# 03_-_MCU.net
KiCad netlist of a schematic drawn in Altium Designer
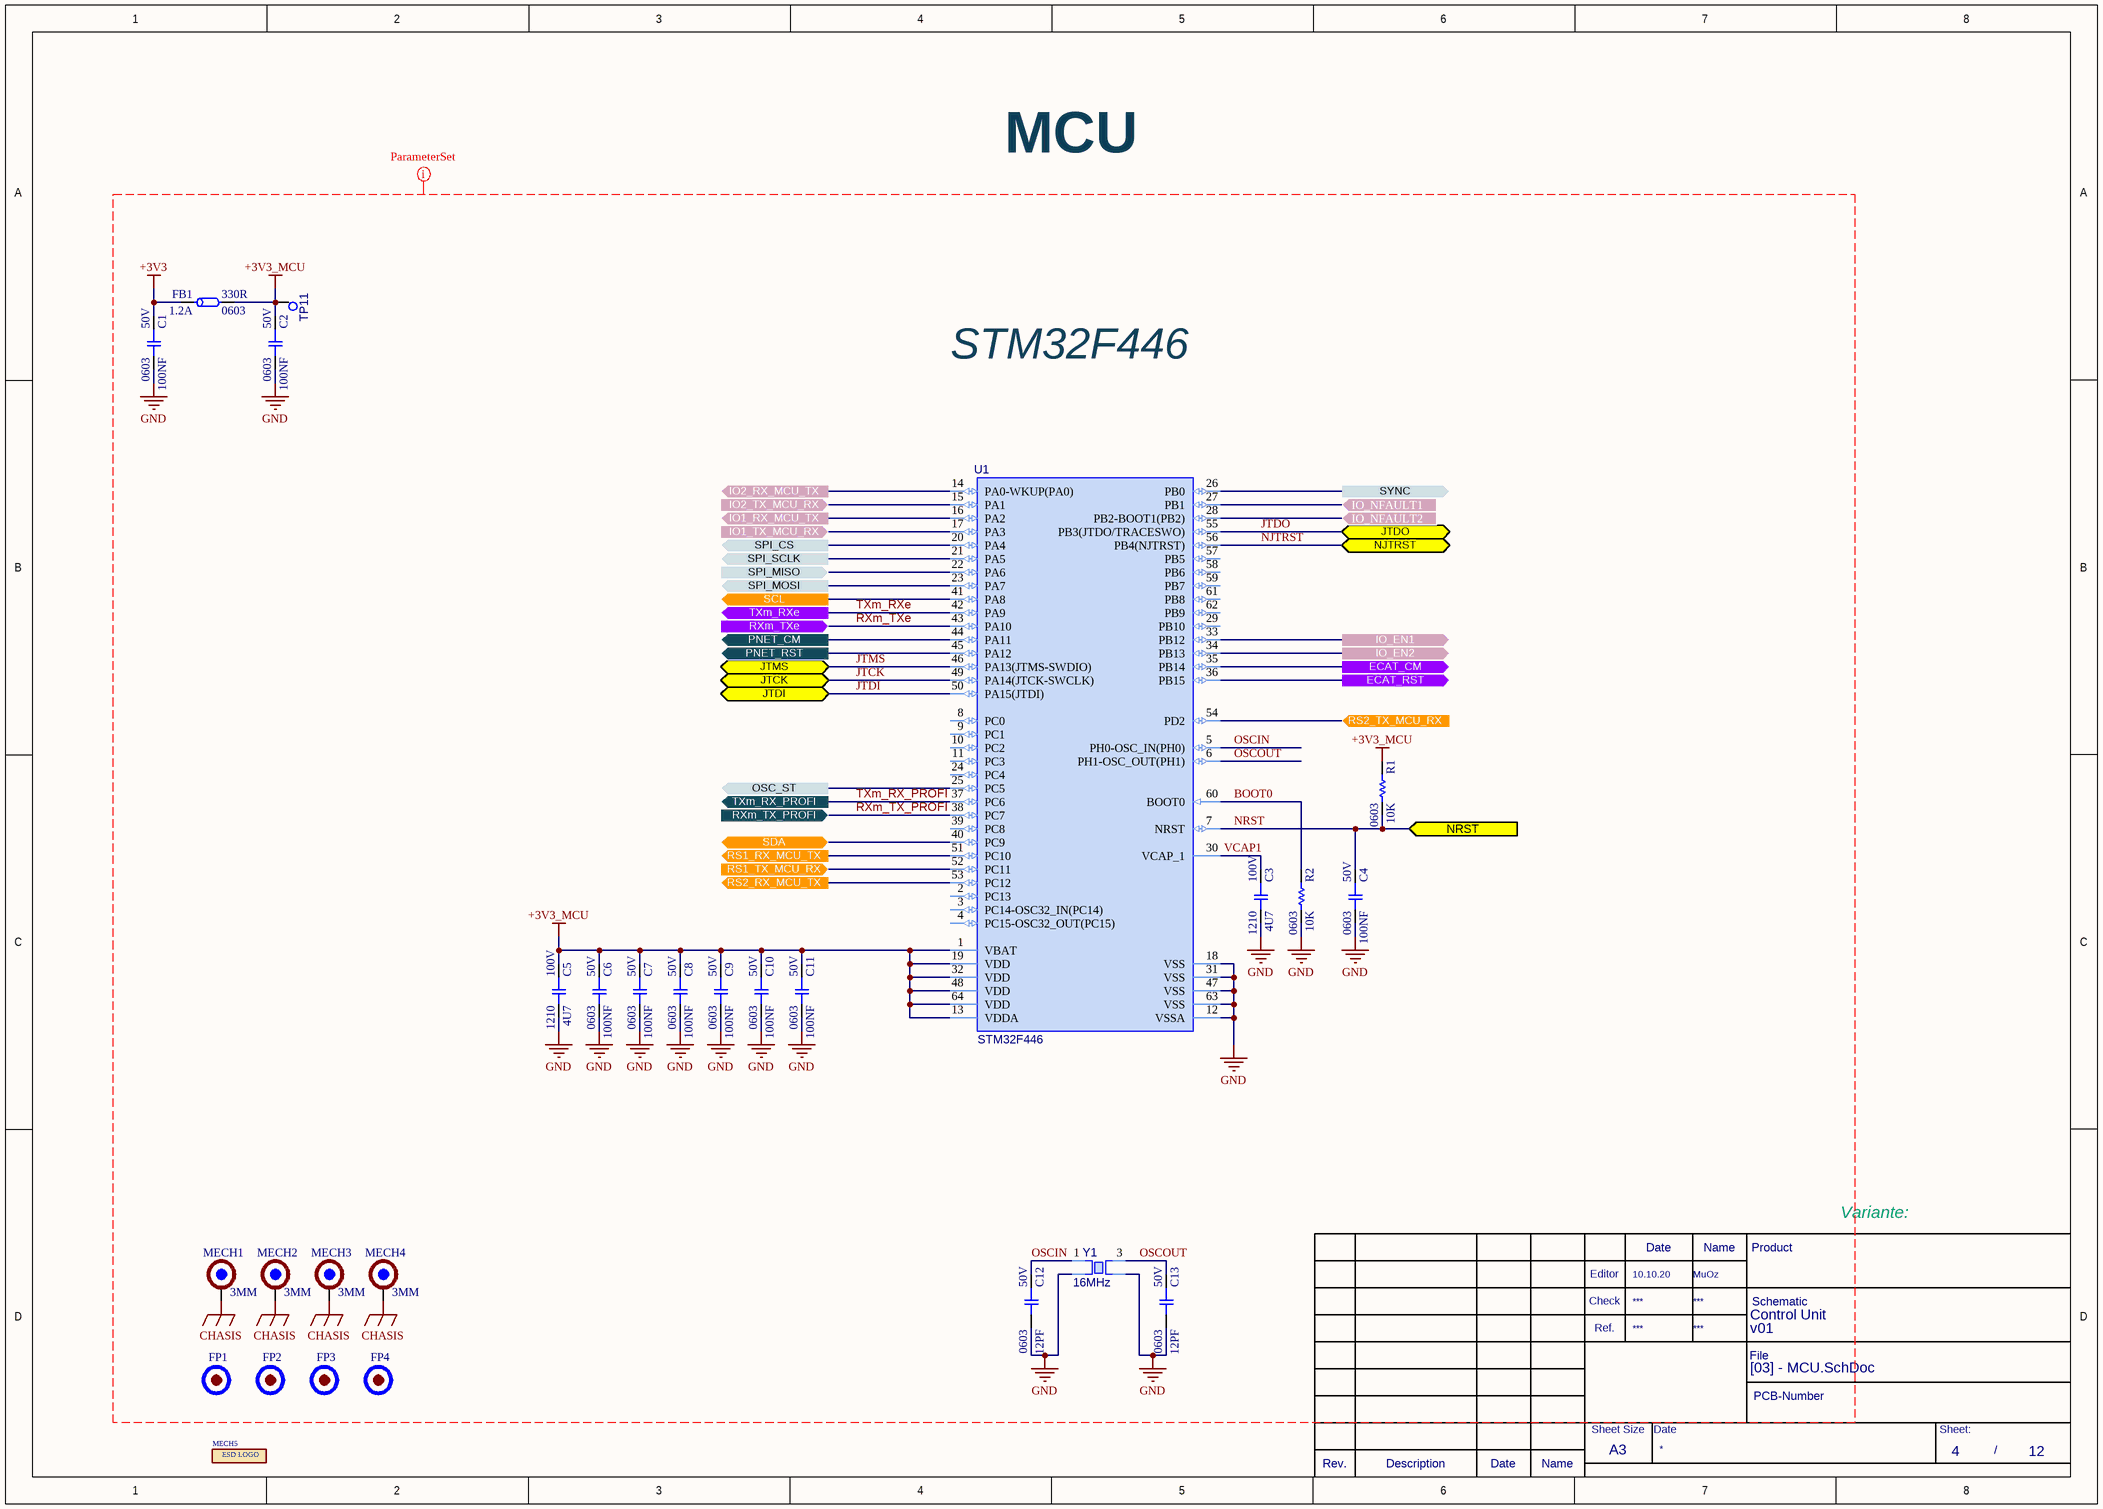
[diagram p0: [03] - MCU.SchDoc]

(export (version "E")
  (design (tool "Eeschema 10.0.6"))
  (components
    (comp (ref "C1")
      (value "100NF")
      (footprint "C-0603")
      (description "CAP CER 0.1UF 50V X7R 0603")
      (fields
        (field (name "MANUFACTURER") "TDK")
        (field (name "MANUFACTURER PART NUMBER") "C1608X7R1H104K080AA")
        (field (name "VOLTAGE RATING") "50V")
        (field (name "CASE CODE (IMPERIAL)") "0603")
        (field (name ".CREATOR") "F:TALI")
      )
      (libsource (lib "BARKO_SCHLIB") (part "C-100NF-0603"))
    )
    (comp (ref "C2")
      (value "100NF")
      (footprint "C-0603")
      (description "CAP CER 0.1UF 50V X7R 0603")
      (fields
        (field (name "MANUFACTURER") "TDK")
        (field (name "MANUFACTURER PART NUMBER") "C1608X7R1H104K080AA")
        (field (name "VOLTAGE RATING") "50V")
        (field (name "CASE CODE (IMPERIAL)") "0603")
        (field (name ".CREATOR") "F:TALI")
      )
      (libsource (lib "BARKO_SCHLIB") (part "C-100NF-0603"))
    )
    (comp (ref "C3")
      (value "4U7")
      (footprint "C-1210")
      (description "CAP CER 4.7UF 100V X7S 1210")
      (fields
        (field (name "MANUFACTURER") "Taiyo Yuden")
        (field (name "MANUFACTURER PART NUMBER") "HMK325C7475KM-PE")
        (field (name "CASE/PACKAGE") "1210")
        (field (name "VOLTAGE RATING") "100V")
        (field (name ".CREATOR") "M.OZKAN")
      )
      (libsource (lib "BARKO_SCHLIB") (part "C-4U7-1210-100V"))
    )
    (comp (ref "C4")
      (value "100NF")
      (footprint "C-0603")
      (description "CAP CER 0.1UF 50V X7R 0603")
      (fields
        (field (name "MANUFACTURER") "TDK")
        (field (name "MANUFACTURER PART NUMBER") "C1608X7R1H104K080AA")
        (field (name "VOLTAGE RATING") "50V")
        (field (name "CASE CODE (IMPERIAL)") "0603")
        (field (name ".CREATOR") "F:TALI")
      )
      (libsource (lib "BARKO_SCHLIB") (part "C-100NF-0603"))
    )
    (comp (ref "C5")
      (value "4U7")
      (footprint "C-1210")
      (description "CAP CER 4.7UF 100V X7S 1210")
      (fields
        (field (name "MANUFACTURER") "Taiyo Yuden")
        (field (name "MANUFACTURER PART NUMBER") "HMK325C7475KM-PE")
        (field (name "CASE/PACKAGE") "1210")
        (field (name "VOLTAGE RATING") "100V")
        (field (name ".CREATOR") "M.OZKAN")
      )
      (libsource (lib "BARKO_SCHLIB") (part "C-4U7-1210-100V"))
    )
    (comp (ref "C6")
      (value "100NF")
      (footprint "C-0603")
      (description "CAP CER 0.1UF 50V X7R 0603")
      (fields
        (field (name "MANUFACTURER") "TDK")
        (field (name "MANUFACTURER PART NUMBER") "C1608X7R1H104K080AA")
        (field (name "VOLTAGE RATING") "50V")
        (field (name "CASE CODE (IMPERIAL)") "0603")
        (field (name ".CREATOR") "F:TALI")
      )
      (libsource (lib "BARKO_SCHLIB") (part "C-100NF-0603"))
    )
    (comp (ref "C7")
      (value "100NF")
      (footprint "C-0603")
      (description "CAP CER 0.1UF 50V X7R 0603")
      (fields
        (field (name "MANUFACTURER") "TDK")
        (field (name "MANUFACTURER PART NUMBER") "C1608X7R1H104K080AA")
        (field (name "VOLTAGE RATING") "50V")
        (field (name "CASE CODE (IMPERIAL)") "0603")
        (field (name ".CREATOR") "F:TALI")
      )
      (libsource (lib "BARKO_SCHLIB") (part "C-100NF-0603"))
    )
    (comp (ref "C8")
      (value "100NF")
      (footprint "C-0603")
      (description "CAP CER 0.1UF 50V X7R 0603")
      (fields
        (field (name "MANUFACTURER") "TDK")
        (field (name "MANUFACTURER PART NUMBER") "C1608X7R1H104K080AA")
        (field (name "VOLTAGE RATING") "50V")
        (field (name "CASE CODE (IMPERIAL)") "0603")
        (field (name ".CREATOR") "F:TALI")
      )
      (libsource (lib "BARKO_SCHLIB") (part "C-100NF-0603"))
    )
    (comp (ref "C9")
      (value "100NF")
      (footprint "C-0603")
      (description "CAP CER 0.1UF 50V X7R 0603")
      (fields
        (field (name "MANUFACTURER") "TDK")
        (field (name "MANUFACTURER PART NUMBER") "C1608X7R1H104K080AA")
        (field (name "VOLTAGE RATING") "50V")
        (field (name "CASE CODE (IMPERIAL)") "0603")
        (field (name ".CREATOR") "F:TALI")
      )
      (libsource (lib "BARKO_SCHLIB") (part "C-100NF-0603"))
    )
    (comp (ref "C10")
      (value "100NF")
      (footprint "C-0603")
      (description "CAP CER 0.1UF 50V X7R 0603")
      (fields
        (field (name "MANUFACTURER") "TDK")
        (field (name "MANUFACTURER PART NUMBER") "C1608X7R1H104K080AA")
        (field (name "VOLTAGE RATING") "50V")
        (field (name "CASE CODE (IMPERIAL)") "0603")
        (field (name ".CREATOR") "F:TALI")
      )
      (libsource (lib "BARKO_SCHLIB") (part "C-100NF-0603"))
    )
    (comp (ref "C11")
      (value "100NF")
      (footprint "C-0603")
      (description "CAP CER 0.1UF 50V X7R 0603")
      (fields
        (field (name "MANUFACTURER") "TDK")
        (field (name "MANUFACTURER PART NUMBER") "C1608X7R1H104K080AA")
        (field (name "VOLTAGE RATING") "50V")
        (field (name "CASE CODE (IMPERIAL)") "0603")
        (field (name ".CREATOR") "F:TALI")
      )
      (libsource (lib "BARKO_SCHLIB") (part "C-100NF-0603"))
    )
    (comp (ref "C12")
      (value "12PF")
      (footprint "C-0603")
      (description "CAP CER 12PF 50V C0G/NP0 0603")
      (fields
        (field (name "MANUFACTURER") "Samsung")
        (field (name "MANUFACTURER PART NUMBER") "CL10C120JB8NNNC")
        (field (name "CASE CODE (IMPERIAL)") "0603")
        (field (name "VOLTAGE") "50V")
        (field (name ".CREATOR") "M.OZKAN")
      )
      (libsource (lib "BARKO_SCHLIB") (part "C-12PF-0603"))
    )
    (comp (ref "C13")
      (value "12PF")
      (footprint "C-0603")
      (description "CAP CER 12PF 50V C0G/NP0 0603")
      (fields
        (field (name "MANUFACTURER") "Samsung")
        (field (name "MANUFACTURER PART NUMBER") "CL10C120JB8NNNC")
        (field (name "CASE CODE (IMPERIAL)") "0603")
        (field (name "VOLTAGE") "50V")
        (field (name ".CREATOR") "M.OZKAN")
      )
      (libsource (lib "BARKO_SCHLIB") (part "C-12PF-0603"))
    )
    (comp (ref "FB1")
      (value "330R")
      (footprint "FB-0603")
      (description "FERRITE BEAD 330 OHM 0603 1LN")
      (fields
        (field (name "MANUFACTURER") "Murata")
        (field (name "MANUFACTURER PART NUMBER") "BLM18PG331SN1D")
        (field (name "CASE/PACKAGE") "0603")
        (field (name "DC CURRENT") "1.2A")
        (field (name ".CREATOR") "M.OZKAN")
      )
      (libsource (lib "BARKO_SCHLIB") (part "FB-330R-0603"))
    )
    (comp (ref "FP1")
      (value "MECH-Fiducial")
      (footprint "MECH-Fiducial")
      (fields (field (name ".CREATOR") "F:TALI"))
      (libsource (lib "BARKO_SCHLIB") (part "MECH-Fiducial"))
    )
    (comp (ref "FP2")
      (value "MECH-Fiducial")
      (footprint "MECH-Fiducial")
      (fields (field (name ".CREATOR") "F:TALI"))
      (libsource (lib "BARKO_SCHLIB") (part "MECH-Fiducial"))
    )
    (comp (ref "FP3")
      (value "MECH-Fiducial")
      (footprint "MECH-Fiducial")
      (fields (field (name ".CREATOR") "F:TALI"))
      (libsource (lib "BARKO_SCHLIB") (part "MECH-Fiducial"))
    )
    (comp (ref "FP4")
      (value "MECH-Fiducial")
      (footprint "MECH-Fiducial")
      (fields (field (name ".CREATOR") "F:TALI"))
      (libsource (lib "BARKO_SCHLIB") (part "MECH-Fiducial"))
    )
    (comp (ref "MECH1")
      (value "3MM")
      (footprint "MECH-3MM HOLE")
      (fields (field (name ".CREATOR") "F:TALI"))
      (libsource (lib "BARKO_SCHLIB") (part "MECH-3MM HOLE"))
    )
    (comp (ref "MECH2")
      (value "3MM")
      (footprint "MECH-3MM HOLE")
      (fields (field (name ".CREATOR") "F:TALI"))
      (libsource (lib "BARKO_SCHLIB") (part "MECH-3MM HOLE"))
    )
    (comp (ref "MECH3")
      (value "3MM")
      (footprint "MECH-3MM HOLE")
      (fields (field (name ".CREATOR") "F:TALI"))
      (libsource (lib "BARKO_SCHLIB") (part "MECH-3MM HOLE"))
    )
    (comp (ref "MECH4")
      (value "3MM")
      (footprint "MECH-3MM HOLE")
      (fields (field (name ".CREATOR") "F:TALI"))
      (libsource (lib "BARKO_SCHLIB") (part "MECH-3MM HOLE"))
    )
    (comp (ref "MECH5")
      (value "MECH-ESD-LOGO")
      (footprint "ESD_LOGO_4")
      (fields (field (name ".CREATOR") "F:TALI"))
      (libsource (lib "BARKO_SCHLIB") (part "MECH-ESD-LOGO"))
    )
    (comp (ref "R1")
      (value "10K")
      (footprint "R-0603")
      (description "RES SMD 10K OHM 1% 1/10W 0603")
      (fields
        (field (name "MANUFACTURER") "Yageo")
        (field (name "MANUFACTURER PART NUMBER") "RC0603FR-0710KL")
        (field (name "CASE CODE (IMPERIAL)") "0603")
        (field (name ".CREATOR") "F:TALI")
      )
      (libsource (lib "BARKO_SCHLIB") (part "R-10K-0603"))
    )
    (comp (ref "R2")
      (value "10K")
      (footprint "R-0603")
      (description "RES SMD 10K OHM 1% 1/10W 0603")
      (fields
        (field (name "MANUFACTURER") "Yageo")
        (field (name "MANUFACTURER PART NUMBER") "RC0603FR-0710KL")
        (field (name "CASE CODE (IMPERIAL)") "0603")
        (field (name ".CREATOR") "F:TALI")
      )
      (libsource (lib "BARKO_SCHLIB") (part "R-10K-0603"))
    )
    (comp (ref "TP11")
      (value "MECH-TESTPOINT")
      (footprint "MECH-TESTPOINT")
      (fields (field (name ".CREATOR") "F:TALI"))
      (libsource (lib "BARKO_SCHLIB") (part "MECH-TESTPOINT"))
    )
    (comp (ref "U1")
      (value "STM32F446")
      (footprint "STM-LQFP64_M")
      (description "IC MCU 32BIT 256KB FLASH 64LQFP")
      (fields
        (field (name "MANUFACTURER") "STMicroelectronics")
        (field (name "MANUFACTURER PART NUMBER") "STM32F446RCT6TR")
      )
      (libsource (lib "SCHLIB") (part "IC-STM32F446RCT6TR"))
    )
    (comp (ref "Y1")
      (value "16MHz")
      (footprint "CRY-TSX-3225")
      (description "CRYSTAL 16.00 MHZ 9PF SMD")
      (fields
        (field (name "MANUFACTURER") "Epson")
        (field (name "MANUFACTURER PART NUMBER") "TSX-3225 16.0000MF18X-AC0")
      )
      (libsource (lib "SCHLIB") (part "CRYSTAL-TSX-3225 16.0000MF18X-AC0"))
    )
  )
  (nets
    (net (code "1") (name "+3V3") (class "Default")
      (node (ref "C1") (pin "1") (pinfunction "1_1") (pintype "passive"))
      (node (ref "FB1") (pin "1") (pinfunction "1_1") (pintype "passive"))
    )
    (net (code "2") (name "+3V3_MCU") (class "Default")
      (node (ref "C10") (pin "1") (pinfunction "1_1") (pintype "passive"))
      (node (ref "C11") (pin "1") (pinfunction "1_1") (pintype "passive"))
      (node (ref "C2") (pin "1") (pinfunction "1_1") (pintype "passive"))
      (node (ref "C5") (pin "1") (pinfunction "1_1") (pintype "passive"))
      (node (ref "C6") (pin "1") (pinfunction "1_1") (pintype "passive"))
      (node (ref "C7") (pin "1") (pinfunction "1_1") (pintype "passive"))
      (node (ref "C8") (pin "1") (pinfunction "1_1") (pintype "passive"))
      (node (ref "C9") (pin "1") (pinfunction "1_1") (pintype "passive"))
      (node (ref "FB1") (pin "2") (pinfunction "2_2") (pintype "passive"))
      (node (ref "R1") (pin "1") (pinfunction "1_1") (pintype "passive"))
      (node (ref "TP11") (pin "1") (pinfunction "1_1") (pintype "passive"))
      (node (ref "U1") (pin "1") (pinfunction "VBAT_1") (pintype "power_in"))
      (node (ref "U1") (pin "13") (pinfunction "VDDA_13") (pintype "power_in"))
      (node (ref "U1") (pin "19") (pinfunction "VDD_19") (pintype "power_in"))
      (node (ref "U1") (pin "32") (pinfunction "VDD_32") (pintype "power_in"))
      (node (ref "U1") (pin "48") (pinfunction "VDD_48") (pintype "power_in"))
      (node (ref "U1") (pin "64") (pinfunction "VDD_64") (pintype "power_in"))
    )
    (net (code "3") (name "/BOOT0") (class "Default")
      (node (ref "R2") (pin "1") (pinfunction "1_1") (pintype "passive"))
      (node (ref "U1") (pin "60") (pinfunction "BOOT0_60") (pintype "input"))
    )
    (net (code "4") (name "/ECAT_CM") (class "Default")
      (node (ref "U1") (pin "35") (pinfunction "PB14_35") (pintype "bidirectional"))
    )
    (net (code "5") (name "/ECAT_RST") (class "Default")
      (node (ref "U1") (pin "36") (pinfunction "PB15_36") (pintype "bidirectional"))
    )
    (net (code "6") (name "/IO1_RX_MCU_TX") (class "Default")
      (node (ref "U1") (pin "16") (pinfunction "PA2_16") (pintype "bidirectional"))
    )
    (net (code "7") (name "/IO1_TX_MCU_RX") (class "Default")
      (node (ref "U1") (pin "17") (pinfunction "PA3_17") (pintype "bidirectional"))
    )
    (net (code "8") (name "/IO2_RX_MCU_TX") (class "Default")
      (node (ref "U1") (pin "14") (pinfunction "PA0-WKUP(PA0)_14") (pintype "bidirectional"))
    )
    (net (code "9") (name "/IO2_TX_MCU_RX") (class "Default")
      (node (ref "U1") (pin "15") (pinfunction "PA1_15") (pintype "bidirectional"))
    )
    (net (code "10") (name "/IO_EN1") (class "Default")
      (node (ref "U1") (pin "33") (pinfunction "PB12_33") (pintype "bidirectional"))
    )
    (net (code "11") (name "/IO_EN2") (class "Default")
      (node (ref "U1") (pin "34") (pinfunction "PB13_34") (pintype "bidirectional"))
    )
    (net (code "12") (name "/IO_NFAULT1") (class "Default")
      (node (ref "U1") (pin "27") (pinfunction "PB1_27") (pintype "bidirectional"))
    )
    (net (code "13") (name "/IO_NFAULT2") (class "Default")
      (node (ref "U1") (pin "28") (pinfunction "PB2-BOOT1(PB2)_28") (pintype "bidirectional"))
    )
    (net (code "14") (name "/JTCK") (class "Default")
      (node (ref "U1") (pin "49") (pinfunction "PA14(JTCK-SWCLK)_49") (pintype "bidirectional"))
    )
    (net (code "15") (name "/JTDI") (class "Default")
      (node (ref "U1") (pin "50") (pinfunction "PA15(JTDI)_50") (pintype "bidirectional"))
    )
    (net (code "16") (name "/JTDO") (class "Default")
      (node (ref "U1") (pin "55") (pinfunction "PB3(JTDO/TRACESWO)_55") (pintype "bidirectional"))
    )
    (net (code "17") (name "/JTMS") (class "Default")
      (node (ref "U1") (pin "46") (pinfunction "PA13(JTMS-SWDIO)_46") (pintype "bidirectional"))
    )
    (net (code "18") (name "/NJTRST") (class "Default")
      (node (ref "U1") (pin "56") (pinfunction "PB4(NJTRST)_56") (pintype "bidirectional"))
    )
    (net (code "19") (name "/NRST") (class "Default")
      (node (ref "C4") (pin "1") (pinfunction "1_1") (pintype "passive"))
      (node (ref "R1") (pin "2") (pinfunction "2_2") (pintype "passive"))
      (node (ref "U1") (pin "7") (pinfunction "NRST_7") (pintype "bidirectional"))
    )
    (net (code "20") (name "/OSCIN") (class "Default")
      (node (ref "C12") (pin "1") (pinfunction "1_1") (pintype "passive"))
      (node (ref "U1") (pin "5") (pinfunction "PH0-OSC_IN(PH0)_5") (pintype "bidirectional"))
      (node (ref "Y1") (pin "1") (pinfunction "1_1") (pintype "passive"))
    )
    (net (code "21") (name "/OSCOUT") (class "Default")
      (node (ref "C13") (pin "1") (pinfunction "1_1") (pintype "passive"))
      (node (ref "U1") (pin "6") (pinfunction "PH1-OSC_OUT(PH1)_6") (pintype "bidirectional"))
      (node (ref "Y1") (pin "3") (pinfunction "3_3") (pintype "passive"))
    )
    (net (code "22") (name "/OSC_ST") (class "Default")
      (node (ref "U1") (pin "25") (pinfunction "PC5_25") (pintype "bidirectional"))
    )
    (net (code "23") (name "/PNET_CM") (class "Default")
      (node (ref "U1") (pin "44") (pinfunction "PA11_44") (pintype "bidirectional"))
    )
    (net (code "24") (name "/PNET_RST") (class "Default")
      (node (ref "U1") (pin "45") (pinfunction "PA12_45") (pintype "bidirectional"))
    )
    (net (code "25") (name "/RS1_RX_MCU_TX") (class "Default")
      (node (ref "U1") (pin "51") (pinfunction "PC10_51") (pintype "bidirectional"))
    )
    (net (code "26") (name "/RS1_TX_MCU_RX") (class "Default")
      (node (ref "U1") (pin "52") (pinfunction "PC11_52") (pintype "bidirectional"))
    )
    (net (code "27") (name "/RS2_RX_MCU_TX") (class "Default")
      (node (ref "U1") (pin "53") (pinfunction "PC12_53") (pintype "bidirectional"))
    )
    (net (code "28") (name "/RS2_TX_MCU_RX") (class "Default")
      (node (ref "U1") (pin "54") (pinfunction "PD2_54") (pintype "bidirectional"))
    )
    (net (code "29") (name "/RXm_TX_PROFI") (class "Default")
      (node (ref "U1") (pin "38") (pinfunction "PC7_38") (pintype "bidirectional"))
    )
    (net (code "30") (name "/RXm_TXe") (class "Default")
      (node (ref "U1") (pin "43") (pinfunction "PA10_43") (pintype "bidirectional"))
    )
    (net (code "31") (name "/SCL") (class "Default")
      (node (ref "U1") (pin "41") (pinfunction "PA8_41") (pintype "bidirectional"))
    )
    (net (code "32") (name "/SDA") (class "Default")
      (node (ref "U1") (pin "40") (pinfunction "PC9_40") (pintype "bidirectional"))
    )
    (net (code "33") (name "/SPI_CS") (class "Default")
      (node (ref "U1") (pin "20") (pinfunction "PA4_20") (pintype "bidirectional"))
    )
    (net (code "34") (name "/SPI_MISO") (class "Default")
      (node (ref "U1") (pin "22") (pinfunction "PA6_22") (pintype "bidirectional"))
    )
    (net (code "35") (name "/SPI_MOSI") (class "Default")
      (node (ref "U1") (pin "23") (pinfunction "PA7_23") (pintype "bidirectional"))
    )
    (net (code "36") (name "/SPI_SCLK") (class "Default")
      (node (ref "U1") (pin "21") (pinfunction "PA5_21") (pintype "bidirectional"))
    )
    (net (code "37") (name "/SYNC") (class "Default")
      (node (ref "U1") (pin "26") (pinfunction "PB0_26") (pintype "bidirectional"))
    )
    (net (code "38") (name "/TXm_RX_PROFI") (class "Default")
      (node (ref "U1") (pin "37") (pinfunction "PC6_37") (pintype "bidirectional"))
    )
    (net (code "39") (name "/TXm_RXe") (class "Default")
      (node (ref "U1") (pin "42") (pinfunction "PA9_42") (pintype "bidirectional"))
    )
    (net (code "40") (name "/VCAP1") (class "Default")
      (node (ref "C3") (pin "1") (pinfunction "1_1") (pintype "passive"))
      (node (ref "U1") (pin "30") (pinfunction "VCAP_1_30") (pintype "passive"))
    )
    (net (code "41") (name "CHASIS") (class "Default")
      (node (ref "MECH1") (pin "1") (pinfunction "1_1") (pintype "passive"))
      (node (ref "MECH2") (pin "1") (pinfunction "1_1") (pintype "passive"))
      (node (ref "MECH3") (pin "1") (pinfunction "1_1") (pintype "passive"))
      (node (ref "MECH4") (pin "1") (pinfunction "1_1") (pintype "passive"))
    )
    (net (code "42") (name "GND") (class "Default")
      (node (ref "C1") (pin "2") (pinfunction "2_2") (pintype "passive"))
      (node (ref "C10") (pin "2") (pinfunction "2_2") (pintype "passive"))
      (node (ref "C11") (pin "2") (pinfunction "2_2") (pintype "passive"))
      (node (ref "C12") (pin "2") (pinfunction "2_2") (pintype "passive"))
      (node (ref "C13") (pin "2") (pinfunction "2_2") (pintype "passive"))
      (node (ref "C2") (pin "2") (pinfunction "2_2") (pintype "passive"))
      (node (ref "C3") (pin "2") (pinfunction "2_2") (pintype "passive"))
      (node (ref "C4") (pin "2") (pinfunction "2_2") (pintype "passive"))
      (node (ref "C5") (pin "2") (pinfunction "2_2") (pintype "passive"))
      (node (ref "C6") (pin "2") (pinfunction "2_2") (pintype "passive"))
      (node (ref "C7") (pin "2") (pinfunction "2_2") (pintype "passive"))
      (node (ref "C8") (pin "2") (pinfunction "2_2") (pintype "passive"))
      (node (ref "C9") (pin "2") (pinfunction "2_2") (pintype "passive"))
      (node (ref "R2") (pin "2") (pinfunction "2_2") (pintype "passive"))
      (node (ref "U1") (pin "12") (pinfunction "VSSA_12") (pintype "power_in"))
      (node (ref "U1") (pin "18") (pinfunction "VSS_18") (pintype "power_in"))
      (node (ref "U1") (pin "31") (pinfunction "VSS_31") (pintype "power_in"))
      (node (ref "U1") (pin "47") (pinfunction "VSS_47") (pintype "power_in"))
      (node (ref "U1") (pin "63") (pinfunction "VSS_63") (pintype "power_in"))
      (node (ref "Y1") (pin "2") (pinfunction "2_2") (pintype "passive"))
      (node (ref "Y1") (pin "4") (pinfunction "4_4") (pintype "passive"))
    )
    (net (code "43") (name "unconnected-(U1-PB5-Pad57)") (class "Default")
      (node (ref "U1") (pin "57") (pinfunction "PB5_57") (pintype "bidirectional"))
    )
    (net (code "44") (name "unconnected-(U1-PB6-Pad58)") (class "Default")
      (node (ref "U1") (pin "58") (pinfunction "PB6_58") (pintype "bidirectional"))
    )
    (net (code "45") (name "unconnected-(U1-PB7-Pad59)") (class "Default")
      (node (ref "U1") (pin "59") (pinfunction "PB7_59") (pintype "bidirectional"))
    )
    (net (code "46") (name "unconnected-(U1-PB8-Pad61)") (class "Default")
      (node (ref "U1") (pin "61") (pinfunction "PB8_61") (pintype "bidirectional"))
    )
    (net (code "47") (name "unconnected-(U1-PB9-Pad62)") (class "Default")
      (node (ref "U1") (pin "62") (pinfunction "PB9_62") (pintype "bidirectional"))
    )
    (net (code "48") (name "unconnected-(U1-PB10-Pad29)") (class "Default")
      (node (ref "U1") (pin "29") (pinfunction "PB10_29") (pintype "bidirectional"))
    )
    (net (code "49") (name "unconnected-(U1-PC0-Pad8)") (class "Default")
      (node (ref "U1") (pin "8") (pinfunction "PC0_8") (pintype "bidirectional"))
    )
    (net (code "50") (name "unconnected-(U1-PC1-Pad9)") (class "Default")
      (node (ref "U1") (pin "9") (pinfunction "PC1_9") (pintype "bidirectional"))
    )
    (net (code "51") (name "unconnected-(U1-PC2-Pad10)") (class "Default")
      (node (ref "U1") (pin "10") (pinfunction "PC2_10") (pintype "bidirectional"))
    )
    (net (code "52") (name "unconnected-(U1-PC3-Pad11)") (class "Default")
      (node (ref "U1") (pin "11") (pinfunction "PC3_11") (pintype "bidirectional"))
    )
    (net (code "53") (name "unconnected-(U1-PC4-Pad24)") (class "Default")
      (node (ref "U1") (pin "24") (pinfunction "PC4_24") (pintype "bidirectional"))
    )
    (net (code "54") (name "unconnected-(U1-PC8-Pad39)") (class "Default")
      (node (ref "U1") (pin "39") (pinfunction "PC8_39") (pintype "bidirectional"))
    )
    (net (code "55") (name "unconnected-(U1-PC13-Pad2)") (class "Default")
      (node (ref "U1") (pin "2") (pinfunction "PC13_2") (pintype "bidirectional"))
    )
    (net (code "56") (name "unconnected-(U1-PC14-OSC32_IN(PC14)-Pad3)") (class "Default")
      (node (ref "U1") (pin "3") (pinfunction "PC14-OSC32_IN(PC14)_3") (pintype "bidirectional"))
    )
    (net (code "57") (name "unconnected-(U1-PC15-OSC32_OUT(PC15)-Pad4)") (class "Default")
      (node (ref "U1") (pin "4") (pinfunction "PC15-OSC32_OUT(PC15)_4") (pintype "bidirectional"))
    )
  )
)
